# simple-bob-adapter.net
KiCad netlist of a schematic drawn in EAGLE
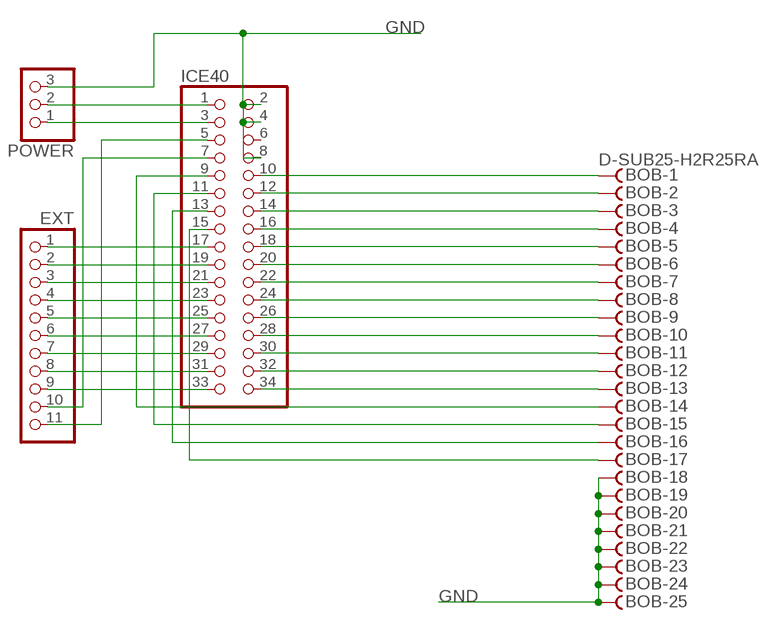
[diagram p0: schematic, sheet 1]

(export (version "E")
  (design (tool "Eeschema 10.0.6"))
  (components
    (comp (ref "BOB")
      (value "D-SUB25-H2R25RA")
      (footprint "eagle-import:H2R25RA")
      (libsource (lib "eagle-import") (part "D-SUB25-H2R25RA"))
    )
    (comp (ref "EXT")
      (value "PINHD-1X11")
      (footprint "eagle-import:1X11")
      (libsource (lib "eagle-import") (part "PINHD-1X11"))
    )
    (comp (ref "ICE40")
      (value "PINHD-2X17/90")
      (footprint "eagle-import:2X17_90")
      (libsource (lib "eagle-import") (part "PINHD-2X17/90"))
    )
    (comp (ref "POWER")
      (value "PINHD-1X3")
      (footprint "eagle-import:1X03")
      (libsource (lib "eagle-import") (part "PINHD-1X3"))
    )
  )
  (nets
    (net (code "1") (name "/GND") (class "Default")
      (node (ref "BOB") (pin "18") (pinfunction "F_18") (pintype "passive"))
      (node (ref "BOB") (pin "19") (pinfunction "F_19") (pintype "passive"))
      (node (ref "BOB") (pin "20") (pinfunction "F_20") (pintype "passive"))
      (node (ref "BOB") (pin "21") (pinfunction "F_21") (pintype "passive"))
      (node (ref "BOB") (pin "22") (pinfunction "F_22") (pintype "passive"))
      (node (ref "BOB") (pin "23") (pinfunction "F_23") (pintype "passive"))
      (node (ref "BOB") (pin "24") (pinfunction "F_24") (pintype "passive"))
      (node (ref "BOB") (pin "25") (pinfunction "F_25") (pintype "passive"))
      (node (ref "ICE40") (pin "2") (pinfunction "2_2") (pintype "passive"))
      (node (ref "ICE40") (pin "4") (pinfunction "4_4") (pintype "passive"))
      (node (ref "ICE40") (pin "8") (pinfunction "8_8") (pintype "passive"))
      (node (ref "POWER") (pin "3") (pinfunction "3_3") (pintype "passive"))
    )
    (net (code "2") (name "Net-(BOBA-F)") (class "Default")
      (node (ref "BOB") (pin "1") (pinfunction "F_1") (pintype "passive"))
      (node (ref "ICE40") (pin "10") (pinfunction "10_10") (pintype "passive"))
    )
    (net (code "3") (name "Net-(BOBB-F)") (class "Default")
      (node (ref "BOB") (pin "10") (pinfunction "F_10") (pintype "passive"))
      (node (ref "ICE40") (pin "28") (pinfunction "28_28") (pintype "passive"))
    )
    (net (code "4") (name "Net-(BOBC-F)") (class "Default")
      (node (ref "BOB") (pin "11") (pinfunction "F_11") (pintype "passive"))
      (node (ref "ICE40") (pin "30") (pinfunction "30_30") (pintype "passive"))
    )
    (net (code "5") (name "Net-(BOBD-F)") (class "Default")
      (node (ref "BOB") (pin "12") (pinfunction "F_12") (pintype "passive"))
      (node (ref "ICE40") (pin "32") (pinfunction "32_32") (pintype "passive"))
    )
    (net (code "6") (name "Net-(BOBE-F)") (class "Default")
      (node (ref "BOB") (pin "13") (pinfunction "F_13") (pintype "passive"))
      (node (ref "ICE40") (pin "34") (pinfunction "34_34") (pintype "passive"))
    )
    (net (code "7") (name "Net-(BOBF-F)") (class "Default")
      (node (ref "BOB") (pin "14") (pinfunction "F_14") (pintype "passive"))
      (node (ref "ICE40") (pin "9") (pinfunction "9_9") (pintype "passive"))
    )
    (net (code "8") (name "Net-(BOBG-F)") (class "Default")
      (node (ref "BOB") (pin "15") (pinfunction "F_15") (pintype "passive"))
      (node (ref "ICE40") (pin "11") (pinfunction "11_11") (pintype "passive"))
    )
    (net (code "9") (name "Net-(BOBH-F)") (class "Default")
      (node (ref "BOB") (pin "16") (pinfunction "F_16") (pintype "passive"))
      (node (ref "ICE40") (pin "13") (pinfunction "13_13") (pintype "passive"))
    )
    (net (code "10") (name "Net-(BOBI-F)") (class "Default")
      (node (ref "BOB") (pin "17") (pinfunction "F_17") (pintype "passive"))
      (node (ref "ICE40") (pin "15") (pinfunction "15_15") (pintype "passive"))
    )
    (net (code "11") (name "Net-(BOBL-F)") (class "Default")
      (node (ref "BOB") (pin "2") (pinfunction "F_2") (pintype "passive"))
      (node (ref "ICE40") (pin "12") (pinfunction "12_12") (pintype "passive"))
    )
    (net (code "12") (name "Net-(BOBS-F)") (class "Default")
      (node (ref "BOB") (pin "3") (pinfunction "F_3") (pintype "passive"))
      (node (ref "ICE40") (pin "14") (pinfunction "14_14") (pintype "passive"))
    )
    (net (code "13") (name "Net-(BOBT-F)") (class "Default")
      (node (ref "BOB") (pin "4") (pinfunction "F_4") (pintype "passive"))
      (node (ref "ICE40") (pin "16") (pinfunction "16_16") (pintype "passive"))
    )
    (net (code "14") (name "Net-(BOBU-F)") (class "Default")
      (node (ref "BOB") (pin "5") (pinfunction "F_5") (pintype "passive"))
      (node (ref "ICE40") (pin "18") (pinfunction "18_18") (pintype "passive"))
    )
    (net (code "15") (name "Net-(BOBV-F)") (class "Default")
      (node (ref "BOB") (pin "6") (pinfunction "F_6") (pintype "passive"))
      (node (ref "ICE40") (pin "20") (pinfunction "20_20") (pintype "passive"))
    )
    (net (code "16") (name "Net-(BOBW-F)") (class "Default")
      (node (ref "BOB") (pin "7") (pinfunction "F_7") (pintype "passive"))
      (node (ref "ICE40") (pin "22") (pinfunction "22_22") (pintype "passive"))
    )
    (net (code "17") (name "Net-(BOBX-F)") (class "Default")
      (node (ref "BOB") (pin "8") (pinfunction "F_8") (pintype "passive"))
      (node (ref "ICE40") (pin "24") (pinfunction "24_24") (pintype "passive"))
    )
    (net (code "18") (name "Net-(BOBY-F)") (class "Default")
      (node (ref "BOB") (pin "9") (pinfunction "F_9") (pintype "passive"))
      (node (ref "ICE40") (pin "26") (pinfunction "26_26") (pintype "passive"))
    )
    (net (code "19") (name "Net-(EXT-Pad1)") (class "Default")
      (node (ref "EXT") (pin "1") (pinfunction "1_1") (pintype "passive"))
      (node (ref "ICE40") (pin "17") (pinfunction "17_17") (pintype "passive"))
    )
    (net (code "20") (name "Net-(EXT-Pad2)") (class "Default")
      (node (ref "EXT") (pin "2") (pinfunction "2_2") (pintype "passive"))
      (node (ref "ICE40") (pin "19") (pinfunction "19_19") (pintype "passive"))
    )
    (net (code "21") (name "Net-(EXT-Pad3)") (class "Default")
      (node (ref "EXT") (pin "3") (pinfunction "3_3") (pintype "passive"))
      (node (ref "ICE40") (pin "21") (pinfunction "21_21") (pintype "passive"))
    )
    (net (code "22") (name "Net-(EXT-Pad4)") (class "Default")
      (node (ref "EXT") (pin "4") (pinfunction "4_4") (pintype "passive"))
      (node (ref "ICE40") (pin "23") (pinfunction "23_23") (pintype "passive"))
    )
    (net (code "23") (name "Net-(EXT-Pad5)") (class "Default")
      (node (ref "EXT") (pin "5") (pinfunction "5_5") (pintype "passive"))
      (node (ref "ICE40") (pin "25") (pinfunction "25_25") (pintype "passive"))
    )
    (net (code "24") (name "Net-(EXT-Pad6)") (class "Default")
      (node (ref "EXT") (pin "6") (pinfunction "6_6") (pintype "passive"))
      (node (ref "ICE40") (pin "27") (pinfunction "27_27") (pintype "passive"))
    )
    (net (code "25") (name "Net-(EXT-Pad7)") (class "Default")
      (node (ref "EXT") (pin "7") (pinfunction "7_7") (pintype "passive"))
      (node (ref "ICE40") (pin "29") (pinfunction "29_29") (pintype "passive"))
    )
    (net (code "26") (name "Net-(EXT-Pad8)") (class "Default")
      (node (ref "EXT") (pin "8") (pinfunction "8_8") (pintype "passive"))
      (node (ref "ICE40") (pin "31") (pinfunction "31_31") (pintype "passive"))
    )
    (net (code "27") (name "Net-(EXT-Pad9)") (class "Default")
      (node (ref "EXT") (pin "9") (pinfunction "9_9") (pintype "passive"))
      (node (ref "ICE40") (pin "33") (pinfunction "33_33") (pintype "passive"))
    )
    (net (code "28") (name "Net-(EXT-Pad10)") (class "Default")
      (node (ref "EXT") (pin "10") (pinfunction "10_10") (pintype "passive"))
      (node (ref "ICE40") (pin "7") (pinfunction "7_7") (pintype "passive"))
    )
    (net (code "29") (name "Net-(EXT-Pad11)") (class "Default")
      (node (ref "EXT") (pin "11") (pinfunction "11_11") (pintype "passive"))
      (node (ref "ICE40") (pin "5") (pinfunction "5_5") (pintype "passive"))
    )
    (net (code "30") (name "Net-(ICE40-Pad1)") (class "Default")
      (node (ref "ICE40") (pin "1") (pinfunction "1_1") (pintype "passive"))
      (node (ref "POWER") (pin "2") (pinfunction "2_2") (pintype "passive"))
    )
    (net (code "31") (name "Net-(ICE40-Pad3)") (class "Default")
      (node (ref "ICE40") (pin "3") (pinfunction "3_3") (pintype "passive"))
      (node (ref "POWER") (pin "1") (pinfunction "1_1") (pintype "passive"))
    )
    (net (code "32") (name "unconnected-(ICE40-Pad6)") (class "Default")
      (node (ref "ICE40") (pin "6") (pinfunction "6_6") (pintype "passive"))
    )
  )
)
